# Sheet2.net
KiCad netlist of a schematic drawn in Altium Designer
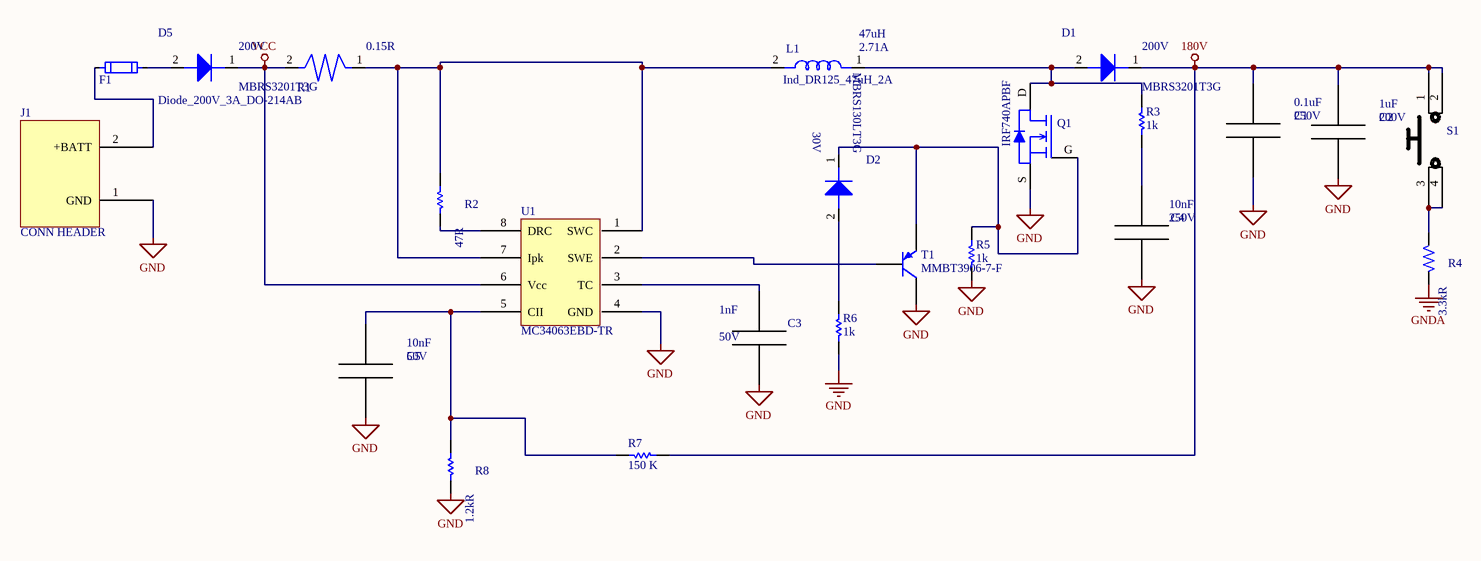
[diagram p0: Sheet2.SchDoc]

(export (version "E")
  (design (tool "Eeschema 10.0.6"))
  (components
    (comp (ref "C1")
      (value "Cap_Cer_0.1u_250V_1206")
      (footprint "CAP_CER_0.1U_250V_1206")
      (description "KEMET - C1206C104KARACTU - CAP, 0.1µF, 250V, 10%, X7R, 1206")
      (fields
        (field (name "MANUFACTURER") "KEMET")
        (field (name "MANUFACTURER PART NUMBER") "C1206C104KARACTU")
      )
      (libsource (lib "Capacitors") (part "Cap_Cer_0.1u_250V_1206"))
    )
    (comp (ref "C2")
      (value "Cap_Cer_1u_200V_2225")
      (footprint "Cap_Cer_1u_200V_2225")
      (description "CAP CER 1UF 200V X7R 2225")
      (fields
        (field (name "MANUFACTURER") "Vishay Vitramon")
        (field (name "MANUFACTURER PART NUMBER") "VJ2225Y105KXCAT")
      )
      (libsource (lib "Capacitors") (part "Cap_Cer_1u_200V_2225"))
    )
    (comp (ref "C3")
      (value "Cap_Cer_1n_50V_0603")
      (footprint "Cap_Cer 1n_50V_0603")
      (description "MURATA - GRM188R71H102KA01D - CAP, MLCC, X7R, 1NF, 50V, 0603, REEL")
      (fields
        (field (name "MANUFACTURER") "Murata")
        (field (name "MANUFACTURER PART NUMBER") "GRM188R71H102KA01D")
      )
      (libsource (lib "Capacitors") (part "Cap_Cer_1n_50V_0603"))
    )
    (comp (ref "C4")
      (value "Cap_Cer_10nF_250V_0805")
      (footprint "CAP_CER_10N_250V_0805")
      (description "Capacitors; Ceramic SMT; Tip and Ring; .010uF 250V; 10%; X7R; TR")
      (fields
        (field (name "MANUFACTURER") "KEMET")
        (field (name "MANUFACTURER PART NUMBER") "C0805C103KARACTU")
      )
      (libsource (lib "Capacitors") (part "Cap_Cer_10nF_250V_0805"))
    )
    (comp (ref "C5")
      (value "Cap_Cer_10n_50V_0603")
      (footprint "Cap_Cer_10n_50V_0603")
      (fields
        (field (name "MANUFACTURER") "Murata")
        (field (name "MANUFACTURER PART NUMBER") "GRM188R71H103KA01D")
        (field (name "TOLERANCE") "10%")
      )
      (libsource (lib "Capacitors") (part "Cap_Cer_10n_50V_0603"))
    )
    (comp (ref "D1")
      (value "Diode_200V_3A_DO-214AB")
      (footprint "D320")
      (fields
        (field (name "MANUFACTURER") "ON Semiconductor")
        (field (name "MANUFACTURER PART NUMBER") "MBRS3201T3G")
      )
      (libsource (lib "Schlib1") (part "Diode_200V_3A_DO-214AB"))
    )
    (comp (ref "D2")
      (value "Diode_30V_2A_DO_214AA")
      (footprint "D130")
      (fields
        (field (name "MANUFACTURER") "ON Semiconductor")
        (field (name "MANUFACTURER PART NUMBER") "MBRS130LT3G")
      )
      (libsource (lib "Schlib1") (part "Diode_30V_2A_DO_214AA"))
    )
    (comp (ref "D5")
      (value "Diode_200V_3A_DO-214AB")
      (footprint "D320")
      (fields
        (field (name "MANUFACTURER") "ON Semiconductor")
        (field (name "MANUFACTURER PART NUMBER") "MBRS3201T3G")
      )
      (libsource (lib "Schlib1") (part "Diode_200V_3A_DO-214AB"))
    )
    (comp (ref "F1")
      (value "Fuseholder(Cartridge)")
      (footprint "FuseHolder")
      (description "Fuse Holder 10A 500VDC Solder Pin Through Hole Bulk Cartridge")
      (fields (field (name "MANUFACTURER") "Schurter") (field (name "MANUFACTURER PART NUMBER") "00318201"))
      (libsource (lib "fuse_holder") (part "Fuseholder(Cartridge)"))
    )
    (comp (ref "J1")
      (value "CONN HEADER")
      (footprint "CONN HEADER R_A 2POS 2.54MM")
      (description "Conn Wire to Board HDR 2 POS 2.54mm Solder RA Thru-Hole Bag")
      (libsource (lib "kicker_andrei") (part "CONN HEADER R_A 2POS 2.54MM"))
    )
    (comp (ref "L1")
      (value "Ind_DR125_47uH_2A")
      (footprint "DR125")
      (description "FIXED IND 47UH 2.71A 74 MOHM SMD")
      (fields
        (field (name "MANUFACTURER") "Eaton Cooper")
        (field (name "MANUFACTURER PART NUMBER") "DR125-470-R")
      )
      (libsource (lib "Schlib1") (part "Ind_DR125_47uH_2A"))
    )
    (comp (ref "Q1")
      (value "IRF740APBF")
      (footprint "To-220")
      (fields (field (name "MANUFACTURER") "Vishay"))
      (libsource (lib "Transistors") (part "IRF740APBF"))
    )
    (comp (ref "R1")
      (value "RES_0.15R_2W_2512")
      (footprint "R2512")
      (fields
        (field (name "MANUFACTURER") "TE Connectivity")
        (field (name "MANUFACTURER PART NUMBER") "RLP73K3AR15JTE")
        (field (name "TOLERANCE") "5%")
      )
      (libsource (lib "Schlib1") (part "RES_0.15R_2W_2512"))
    )
    (comp (ref "R2")
      (value "Res_47R_0805")
      (footprint "0805")
      (description "RES SMD 47 OHM 5% 1/8W 0805")
      (fields
        (field (name "MANUFACTURER") "Stackpole Electronics")
        (field (name "MANUFACTURER PART NUMBER") "RMCF0805JT47R0")
      )
      (libsource (lib "Resistors") (part "Res_47R_0805"))
    )
    (comp (ref "R3")
      (value "1k")
      (footprint "Resistor_0805")
      (description "RES SMD 0805 1k 1/8W")
      (libsource (lib "Resistors") (part "Res_1k_0805"))
    )
    (comp (ref "R4")
      (value "3.3K OHMS 2512")
      (footprint "RESISTOR_2512")
      (description "RES SMD 3.3K OHM 1% 2W 2512")
      (fields (field (name "TOLERANCE") "1%"))
      (libsource (lib "kicker_andrei") (part "RES 3.3K OHM 2512"))
    )
    (comp (ref "R5")
      (value "1k")
      (footprint "Resistor_0805")
      (description "RES SMD 0805 1k 1/8W")
      (libsource (lib "Resistors") (part "Res_1k_0805"))
    )
    (comp (ref "R6")
      (value "1k")
      (footprint "Resistor_0805")
      (description "RES SMD 0805 1k 1/8W")
      (libsource (lib "Resistors") (part "Res_1k_0805"))
    )
    (comp (ref "R7")
      (value "150 K")
      (footprint "Resistor_0805")
      (description "RES SMD 150K 0.125W 0805")
      (libsource (lib "Resistors") (part "Res_150k_0805"))
    )
    (comp (ref "R8")
      (value "Res_1.2K_0805_1%")
      (footprint "0805")
      (description "PANASONIC ELECTRONIC COMPONENTS - ERJ6ENF1201V - RES, THICK FILM, 1K2, 125MW, 1%, REEL")
      (fields
        (field (name "MANUFACTURER") "Panasonic")
        (field (name "MANUFACTURER PART NUMBER") "ERJ-6ENF1201V")
      )
      (libsource (lib "Resistors") (part "Res_1.2K_0805_1%"))
    )
    (comp (ref "S1")
      (value "B3F-1005")
      (footprint "SWITCH_TACTILE_SPST-NO_0.05A_24V")
      (description "Switch Tactile N.O. SPST Flat Plunger PC Pins 0.05A 24VDC 2.55N Thru-Hole Bag")
      (fields (field (name "MANUFACTURER") "Omron"))
      (libsource (lib "Switches") (part "B3F-1005"))
    )
    (comp (ref "T1")
      (value "MMBT3906-7-F")
      (footprint "SOT-23-3")
      (description "TRANS PNP 40V 0.2A SOT23-3")
      (fields (field (name "MANUFACTURER") "Diodes Zetex"))
      (libsource (lib "Transistors") (part "MMBT3906-7-F"))
    )
    (comp (ref "U1")
      (value "MC34063EBD-TR")
      (footprint "MC34063EBD-TR")
      (description "Conv DC-DC Step Down/Step Up 3V to 40V 8-Pin SO N T/R")
      (fields (field (name "MANUFACTURER") "STMicroelectronics"))
      (libsource (lib "Regulators") (part "MC34063EBD-TR"))
    )
  )
  (nets
    (net (code "1") (name "180V") (class "Default")
      (node (ref "C1") (pin "1") (pintype "passive"))
      (node (ref "C2") (pin "1") (pintype "passive"))
      (node (ref "D1") (pin "1") (pinfunction "1_1") (pintype "passive"))
      (node (ref "R7") (pin "1") (pinfunction "1_1") (pintype "passive"))
      (node (ref "S1") (pin "1") (pinfunction "1_1") (pintype "passive"))
      (node (ref "S1") (pin "2") (pinfunction "2_2") (pintype "passive"))
    )
    (net (code "2") (name "GND") (class "Default")
      (node (ref "C1") (pin "2") (pintype "passive"))
      (node (ref "C2") (pin "2") (pintype "passive"))
      (node (ref "C3") (pin "2") (pintype "passive"))
      (node (ref "C4") (pin "2") (pintype "passive"))
      (node (ref "C5") (pin "2") (pintype "passive"))
      (node (ref "J1") (pin "1") (pinfunction "GND_1") (pintype "passive"))
      (node (ref "Q1") (pin "S") (pinfunction "S_S") (pintype "passive"))
      (node (ref "R5") (pin "1") (pinfunction "1_1") (pintype "passive"))
      (node (ref "R6") (pin "1") (pinfunction "1_1") (pintype "passive"))
      (node (ref "R8") (pin "1") (pinfunction "1_1") (pintype "passive"))
      (node (ref "T1") (pin "C") (pinfunction "C_C") (pintype "passive"))
      (node (ref "U1") (pin "4") (pinfunction "GND_4") (pintype "passive"))
    )
    (net (code "3") (name "GNDA") (class "Default")
      (node (ref "R4") (pin "2") (pinfunction "2_2") (pintype "passive"))
    )
    (net (code "4") (name "Net-(C4-Pad1)") (class "Default")
      (node (ref "C4") (pin "1") (pintype "passive"))
      (node (ref "R3") (pin "1") (pinfunction "1_1") (pintype "passive"))
    )
    (net (code "5") (name "Net-(D1-Pad2)") (class "Default")
      (node (ref "D1") (pin "2") (pinfunction "2_2") (pintype "passive"))
      (node (ref "L1") (pin "1") (pinfunction "1_1") (pintype "passive"))
      (node (ref "Q1") (pin "D") (pinfunction "D_D") (pintype "passive"))
      (node (ref "R3") (pin "2") (pinfunction "2_2") (pintype "passive"))
    )
    (net (code "6") (name "Net-(D2-Pad1)") (class "Default")
      (node (ref "D2") (pin "1") (pinfunction "1_1") (pintype "passive"))
      (node (ref "Q1") (pin "G") (pinfunction "G_G") (pintype "passive"))
      (node (ref "R5") (pin "2") (pinfunction "2_2") (pintype "passive"))
      (node (ref "T1") (pin "E") (pinfunction "E_E") (pintype "passive"))
    )
    (net (code "7") (name "Net-(D2-Pad2)") (class "Default")
      (node (ref "D2") (pin "2") (pinfunction "2_2") (pintype "passive"))
      (node (ref "R6") (pin "2") (pinfunction "2_2") (pintype "passive"))
    )
    (net (code "8") (name "Net-(D5-Pad2)") (class "Default")
      (node (ref "D5") (pin "2") (pinfunction "2_2") (pintype "passive"))
      (node (ref "F1") (pin "1") (pinfunction "1_1") (pintype "passive"))
    )
    (net (code "9") (name "Net-(J1-+BATT)") (class "Default")
      (node (ref "F1") (pin "2") (pinfunction "2_2") (pintype "passive"))
      (node (ref "J1") (pin "2") (pinfunction "+BATT_2") (pintype "passive"))
    )
    (net (code "10") (name "Net-(R4-Pad1)") (class "Default")
      (node (ref "R4") (pin "1") (pinfunction "1_1") (pintype "passive"))
      (node (ref "S1") (pin "3") (pinfunction "3_3") (pintype "passive"))
      (node (ref "S1") (pin "4") (pinfunction "4_4") (pintype "passive"))
    )
    (net (code "11") (name "Net-(U1-CII)") (class "Default")
      (node (ref "C5") (pin "1") (pintype "passive"))
      (node (ref "R7") (pin "2") (pinfunction "2_2") (pintype "passive"))
      (node (ref "R8") (pin "2") (pinfunction "2_2") (pintype "passive"))
      (node (ref "U1") (pin "5") (pinfunction "CII_5") (pintype "passive"))
    )
    (net (code "12") (name "Net-(U1-DRC)") (class "Default")
      (node (ref "R2") (pin "1") (pinfunction "1_1") (pintype "passive"))
      (node (ref "U1") (pin "8") (pinfunction "DRC_8") (pintype "passive"))
    )
    (net (code "13") (name "Net-(U1-Ipk)") (class "Default")
      (node (ref "L1") (pin "2") (pinfunction "2_2") (pintype "passive"))
      (node (ref "R1") (pin "1") (pinfunction "1_1") (pintype "passive"))
      (node (ref "R2") (pin "2") (pinfunction "2_2") (pintype "passive"))
      (node (ref "U1") (pin "1") (pinfunction "SWC_1") (pintype "passive"))
      (node (ref "U1") (pin "7") (pinfunction "Ipk_7") (pintype "passive"))
    )
    (net (code "14") (name "Net-(U1-SWE)") (class "Default")
      (node (ref "T1") (pin "B") (pinfunction "B_B") (pintype "passive"))
      (node (ref "U1") (pin "2") (pinfunction "SWE_2") (pintype "passive"))
    )
    (net (code "15") (name "Net-(U1-TC)") (class "Default")
      (node (ref "C3") (pin "1") (pintype "passive"))
      (node (ref "U1") (pin "3") (pinfunction "TC_3") (pintype "passive"))
    )
    (net (code "16") (name "VCC") (class "Default")
      (node (ref "D5") (pin "1") (pinfunction "1_1") (pintype "passive"))
      (node (ref "R1") (pin "2") (pinfunction "2_2") (pintype "passive"))
      (node (ref "U1") (pin "6") (pinfunction "Vcc_6") (pintype "passive"))
    )
  )
)
